# On-Off_Switch.net
KiCad netlist of a schematic drawn in Altium Designer
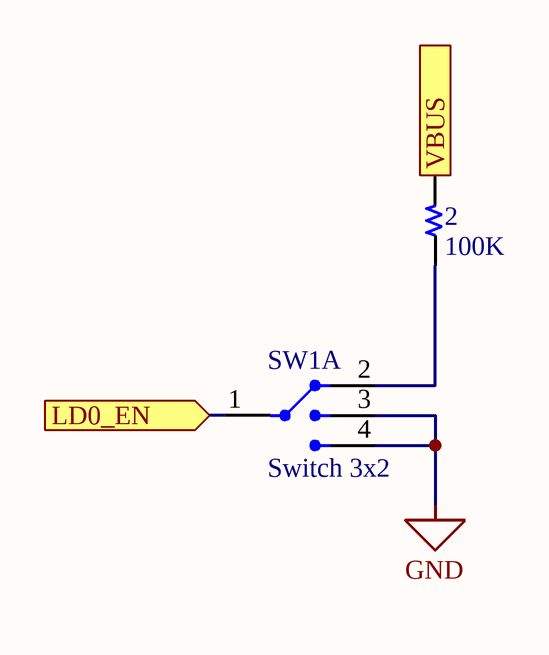
[diagram p0: On-Off Switch.SchDoc]

(export (version "E")
  (design (tool "Eeschema 10.0.6"))
  (components
    (comp (ref "2")
      (value "100K")
      (footprint "R 0805")
      (description "Resistor")
      (libsource (lib "chipfc_libs") (part "Resistor"))
    )
    (comp (ref "SW1")
      (value "Switch 3x2")
      (footprint "SW3X2")
      (libsource (lib "Devzone_SCHLib") (part "SW3x2"))
    )
  )
  (nets
    (net (code "1") (name "/LD0_EN") (class "Default")
      (node (ref "SW1") (pin "1") (pinfunction "Com_1") (pintype "passive"))
    )
    (net (code "2") (name "/VBUS") (class "Default")
      (node (ref "2") (pin "2") (pinfunction "2_2") (pintype "passive"))
    )
    (net (code "3") (name "GND") (class "Default")
      (node (ref "SW1") (pin "3") (pinfunction "I/O2_3") (pintype "passive"))
      (node (ref "SW1") (pin "4") (pinfunction "I/O3_4") (pintype "passive"))
    )
    (net (code "4") (name "Net-(SW1A-I{slash}O1)") (class "Default")
      (node (ref "2") (pin "1") (pinfunction "1_1") (pintype "passive"))
      (node (ref "SW1") (pin "2") (pinfunction "I/O1_2") (pintype "passive"))
    )
  )
)
